# v1-alarm.net
KiCad netlist of a schematic drawn in EAGLE
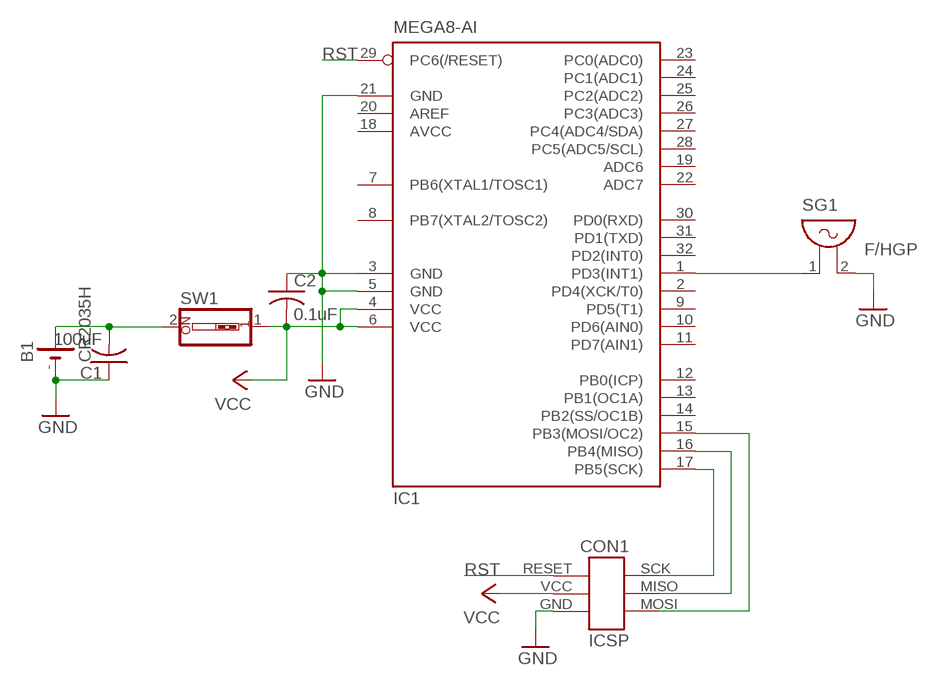
[diagram p0: schematic, sheet 1]

(export (version "E")
  (design (tool "Eeschema 10.0.6"))
  (components
    (comp (ref "B1")
      (value "CR2035H")
      (footprint "eagle-import:CR2032H")
      (libsource (lib "eagle-import") (part "CR2035H"))
    )
    (comp (ref "C1")
      (value "100uF")
      (footprint "eagle-import:C2220K")
      (libsource (lib "eagle-import") (part "C-USC2220K"))
    )
    (comp (ref "C2")
      (value "0.1uF")
      (footprint "eagle-import:C0603")
      (libsource (lib "eagle-import") (part "C-USC0603"))
    )
    (comp (ref "CON1")
      (value "ICSP-HEADER")
      (footprint "eagle-import:ICSP-HEADER")
      (libsource (lib "eagle-import") (part "ICSP-HEADER"))
    )
    (comp (ref "IC1")
      (value "MEGA8-AI")
      (footprint "eagle-import:TQFP32-08")
      (fields (field (name "MPN") "ATMEGA8-16AU"))
      (libsource (lib "eagle-import") (part "MEGA8-AI"))
    )
    (comp (ref "SG1")
      (value "F/HGP")
      (footprint "eagle-import:F_HGP")
      (libsource (lib "eagle-import") (part "F/HGP"))
    )
    (comp (ref "SW1")
      (value "SW_DIP-1")
      (footprint "eagle-import:EDG-01")
      (libsource (lib "eagle-import") (part "SW_DIP-1"))
    )
  )
  (nets
    (net (code "1") (name "/AVCC") (class "Default")
      (node (ref "IC1") (pin "18") (pinfunction "AVCC_18") (pintype "power_in"))
    )
    (net (code "2") (name "/RST") (class "Default")
      (node (ref "CON1") (pin "RESET") (pinfunction "RESET_RESET") (pintype "bidirectional"))
      (node (ref "IC1") (pin "29") (pinfunction "PC6(/RESET)_29") (pintype "bidirectional"))
    )
    (net (code "3") (name "GND") (class "Default")
      (node (ref "B1") (pin "-") (pinfunction "-_-") (pintype "passive"))
      (node (ref "C1") (pin "1") (pinfunction "1_1") (pintype "passive"))
      (node (ref "C2") (pin "1") (pinfunction "1_1") (pintype "passive"))
      (node (ref "CON1") (pin "GND") (pinfunction "GND_GND") (pintype "bidirectional"))
      (node (ref "IC1") (pin "21") (pinfunction "GND_21") (pintype "power_in"))
      (node (ref "IC1") (pin "3") (pinfunction "GND_3") (pintype "power_in"))
      (node (ref "IC1") (pin "5") (pinfunction "GND_5") (pintype "power_in"))
      (node (ref "SG1") (pin "2") (pinfunction "2_2") (pintype "passive"))
    )
    (net (code "4") (name "Net-(B1-Pad+)") (class "Default")
      (node (ref "B1") (pin "+") (pinfunction "+_+") (pintype "passive"))
      (node (ref "C1") (pin "2") (pinfunction "2_2") (pintype "passive"))
      (node (ref "SW1") (pin "2") (pinfunction "2_2") (pintype "passive"))
    )
    (net (code "5") (name "Net-(IC1-PB3(MOSI{slash}OC2))") (class "Default")
      (node (ref "CON1") (pin "MOSI") (pinfunction "MOSI_MOSI") (pintype "bidirectional"))
      (node (ref "IC1") (pin "15") (pinfunction "PB3(MOSI/OC2)_15") (pintype "bidirectional"))
    )
    (net (code "6") (name "Net-(IC1-PB4(MISO))") (class "Default")
      (node (ref "CON1") (pin "MISO") (pinfunction "MISO_MISO") (pintype "bidirectional"))
      (node (ref "IC1") (pin "16") (pinfunction "PB4(MISO)_16") (pintype "bidirectional"))
    )
    (net (code "7") (name "Net-(IC1-PB5(SCK))") (class "Default")
      (node (ref "CON1") (pin "SCK") (pinfunction "SCK_SCK") (pintype "bidirectional"))
      (node (ref "IC1") (pin "17") (pinfunction "PB5(SCK)_17") (pintype "bidirectional"))
    )
    (net (code "8") (name "Net-(IC1-PD3(INT1))") (class "Default")
      (node (ref "IC1") (pin "1") (pinfunction "PD3(INT1)_1") (pintype "bidirectional"))
      (node (ref "SG1") (pin "1") (pinfunction "1_1") (pintype "passive"))
    )
    (net (code "9") (name "VCC") (class "Default")
      (node (ref "C2") (pin "2") (pinfunction "2_2") (pintype "passive"))
      (node (ref "CON1") (pin "VCC") (pinfunction "+5V_VCC") (pintype "bidirectional"))
      (node (ref "IC1") (pin "4") (pinfunction "VCC_4") (pintype "power_in"))
      (node (ref "IC1") (pin "6") (pinfunction "VCC_6") (pintype "power_in"))
      (node (ref "SW1") (pin "1") (pinfunction "1_1") (pintype "passive"))
    )
    (net (code "10") (name "unconnected-(IC1-ADC6-Pad19)") (class "Default")
      (node (ref "IC1") (pin "19") (pinfunction "ADC6_19") (pintype "bidirectional"))
    )
    (net (code "11") (name "unconnected-(IC1-ADC7-Pad22)") (class "Default")
      (node (ref "IC1") (pin "22") (pinfunction "ADC7_22") (pintype "bidirectional"))
    )
    (net (code "12") (name "unconnected-(IC1-AREF-Pad20)") (class "Default")
      (node (ref "IC1") (pin "20") (pinfunction "AREF_20") (pintype "passive"))
    )
    (net (code "13") (name "unconnected-(IC1-PB0(ICP)-Pad12)") (class "Default")
      (node (ref "IC1") (pin "12") (pinfunction "PB0(ICP)_12") (pintype "bidirectional"))
    )
    (net (code "14") (name "unconnected-(IC1-PB1(OC1A)-Pad13)") (class "Default")
      (node (ref "IC1") (pin "13") (pinfunction "PB1(OC1A)_13") (pintype "bidirectional"))
    )
    (net (code "15") (name "unconnected-(IC1-PB2(SS{slash}OC1B)-Pad14)") (class "Default")
      (node (ref "IC1") (pin "14") (pinfunction "PB2(SS/OC1B)_14") (pintype "bidirectional"))
    )
    (net (code "16") (name "unconnected-(IC1-PB6(XTAL1{slash}TOSC1)-Pad7)") (class "Default")
      (node (ref "IC1") (pin "7") (pinfunction "PB6(XTAL1/TOSC1)_7") (pintype "bidirectional"))
    )
    (net (code "17") (name "unconnected-(IC1-PB7(XTAL2{slash}TOSC2)-Pad8)") (class "Default")
      (node (ref "IC1") (pin "8") (pinfunction "PB7(XTAL2/TOSC2)_8") (pintype "bidirectional"))
    )
    (net (code "18") (name "unconnected-(IC1-PC0(ADC0)-Pad23)") (class "Default")
      (node (ref "IC1") (pin "23") (pinfunction "PC0(ADC0)_23") (pintype "bidirectional"))
    )
    (net (code "19") (name "unconnected-(IC1-PC1(ADC1)-Pad24)") (class "Default")
      (node (ref "IC1") (pin "24") (pinfunction "PC1(ADC1)_24") (pintype "bidirectional"))
    )
    (net (code "20") (name "unconnected-(IC1-PC2(ADC2)-Pad25)") (class "Default")
      (node (ref "IC1") (pin "25") (pinfunction "PC2(ADC2)_25") (pintype "bidirectional"))
    )
    (net (code "21") (name "unconnected-(IC1-PC3(ADC3)-Pad26)") (class "Default")
      (node (ref "IC1") (pin "26") (pinfunction "PC3(ADC3)_26") (pintype "bidirectional"))
    )
    (net (code "22") (name "unconnected-(IC1-PC4(ADC4{slash}SDA)-Pad27)") (class "Default")
      (node (ref "IC1") (pin "27") (pinfunction "PC4(ADC4/SDA)_27") (pintype "bidirectional"))
    )
    (net (code "23") (name "unconnected-(IC1-PC5(ADC5{slash}SCL)-Pad28)") (class "Default")
      (node (ref "IC1") (pin "28") (pinfunction "PC5(ADC5/SCL)_28") (pintype "bidirectional"))
    )
    (net (code "24") (name "unconnected-(IC1-PD0(RXD)-Pad30)") (class "Default")
      (node (ref "IC1") (pin "30") (pinfunction "PD0(RXD)_30") (pintype "bidirectional"))
    )
    (net (code "25") (name "unconnected-(IC1-PD1(TXD)-Pad31)") (class "Default")
      (node (ref "IC1") (pin "31") (pinfunction "PD1(TXD)_31") (pintype "bidirectional"))
    )
    (net (code "26") (name "unconnected-(IC1-PD2(INT0)-Pad32)") (class "Default")
      (node (ref "IC1") (pin "32") (pinfunction "PD2(INT0)_32") (pintype "bidirectional"))
    )
    (net (code "27") (name "unconnected-(IC1-PD4(XCK{slash}T0)-Pad2)") (class "Default")
      (node (ref "IC1") (pin "2") (pinfunction "PD4(XCK/T0)_2") (pintype "bidirectional"))
    )
    (net (code "28") (name "unconnected-(IC1-PD5(T1)-Pad9)") (class "Default")
      (node (ref "IC1") (pin "9") (pinfunction "PD5(T1)_9") (pintype "bidirectional"))
    )
    (net (code "29") (name "unconnected-(IC1-PD6(AIN0)-Pad10)") (class "Default")
      (node (ref "IC1") (pin "10") (pinfunction "PD6(AIN0)_10") (pintype "bidirectional"))
    )
    (net (code "30") (name "unconnected-(IC1-PD7(AIN1)-Pad11)") (class "Default")
      (node (ref "IC1") (pin "11") (pinfunction "PD7(AIN1)_11") (pintype "bidirectional"))
    )
  )
)
